# siren.net
KiCad netlist of a schematic drawn in EAGLE
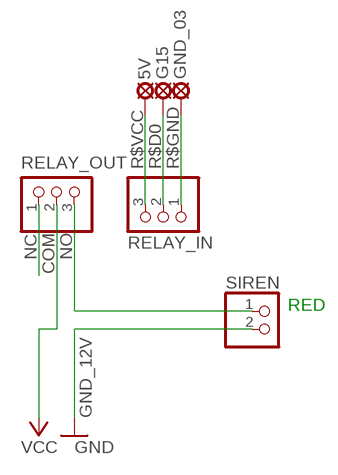
[diagram p0: schematic, sheet 1]

(export (version "E")
  (design (tool "Eeschema 10.0.6"))
  (components
    (comp (ref "5V")
      (value "MCS08")
      (footprint "eagle-import:MCS08")
      (libsource (lib "eagle-import") (part "MCS08"))
    )
    (comp (ref "G15")
      (value "MCS08")
      (footprint "eagle-import:MCS08")
      (libsource (lib "eagle-import") (part "MCS08"))
    )
    (comp (ref "GND_03")
      (value "MCS08")
      (footprint "eagle-import:MCS08")
      (libsource (lib "eagle-import") (part "MCS08"))
    )
    (comp (ref "RELAY_IN")
      (value "PINHD-1X3")
      (footprint "eagle-import:1X03")
      (libsource (lib "eagle-import") (part "PINHD-1X3"))
    )
    (comp (ref "RELAY_OUT")
      (value "PINHD-1X3")
      (footprint "eagle-import:1X03")
      (libsource (lib "eagle-import") (part "PINHD-1X3"))
    )
    (comp (ref "SIREN")
      (value "PINHD-1X2")
      (footprint "eagle-import:1X02")
      (libsource (lib "eagle-import") (part "PINHD-1X2"))
    )
  )
  (nets
    (net (code "1") (name "/NC") (class "Default")
      (node (ref "RELAY_OUT") (pin "1") (pinfunction "1_1") (pintype "passive"))
    )
    (net (code "2") (name "/NO") (class "Default")
      (node (ref "RELAY_OUT") (pin "3") (pinfunction "3_3") (pintype "passive"))
      (node (ref "SIREN") (pin "1") (pinfunction "1_1") (pintype "passive"))
    )
    (net (code "3") (name "/R$D0") (class "Default")
      (node (ref "G15") (pin "MP") (pinfunction "MP_MP") (pintype "passive"))
      (node (ref "RELAY_IN") (pin "2") (pinfunction "2_2") (pintype "passive"))
    )
    (net (code "4") (name "/R$GND") (class "Default")
      (node (ref "GND_03") (pin "MP") (pinfunction "MP_MP") (pintype "passive"))
      (node (ref "RELAY_IN") (pin "1") (pinfunction "1_1") (pintype "passive"))
    )
    (net (code "5") (name "/R$VCC") (class "Default")
      (node (ref "5V") (pin "MP") (pinfunction "MP_MP") (pintype "passive"))
      (node (ref "RELAY_IN") (pin "3") (pinfunction "3_3") (pintype "passive"))
    )
    (net (code "6") (name "GND") (class "Default")
      (node (ref "SIREN") (pin "2") (pinfunction "2_2") (pintype "passive"))
    )
    (net (code "7") (name "VCC") (class "Default")
      (node (ref "RELAY_OUT") (pin "2") (pinfunction "2_2") (pintype "passive"))
    )
  )
)
